# voltage_regulator.net
KiCad netlist of a schematic drawn in EasyEDA
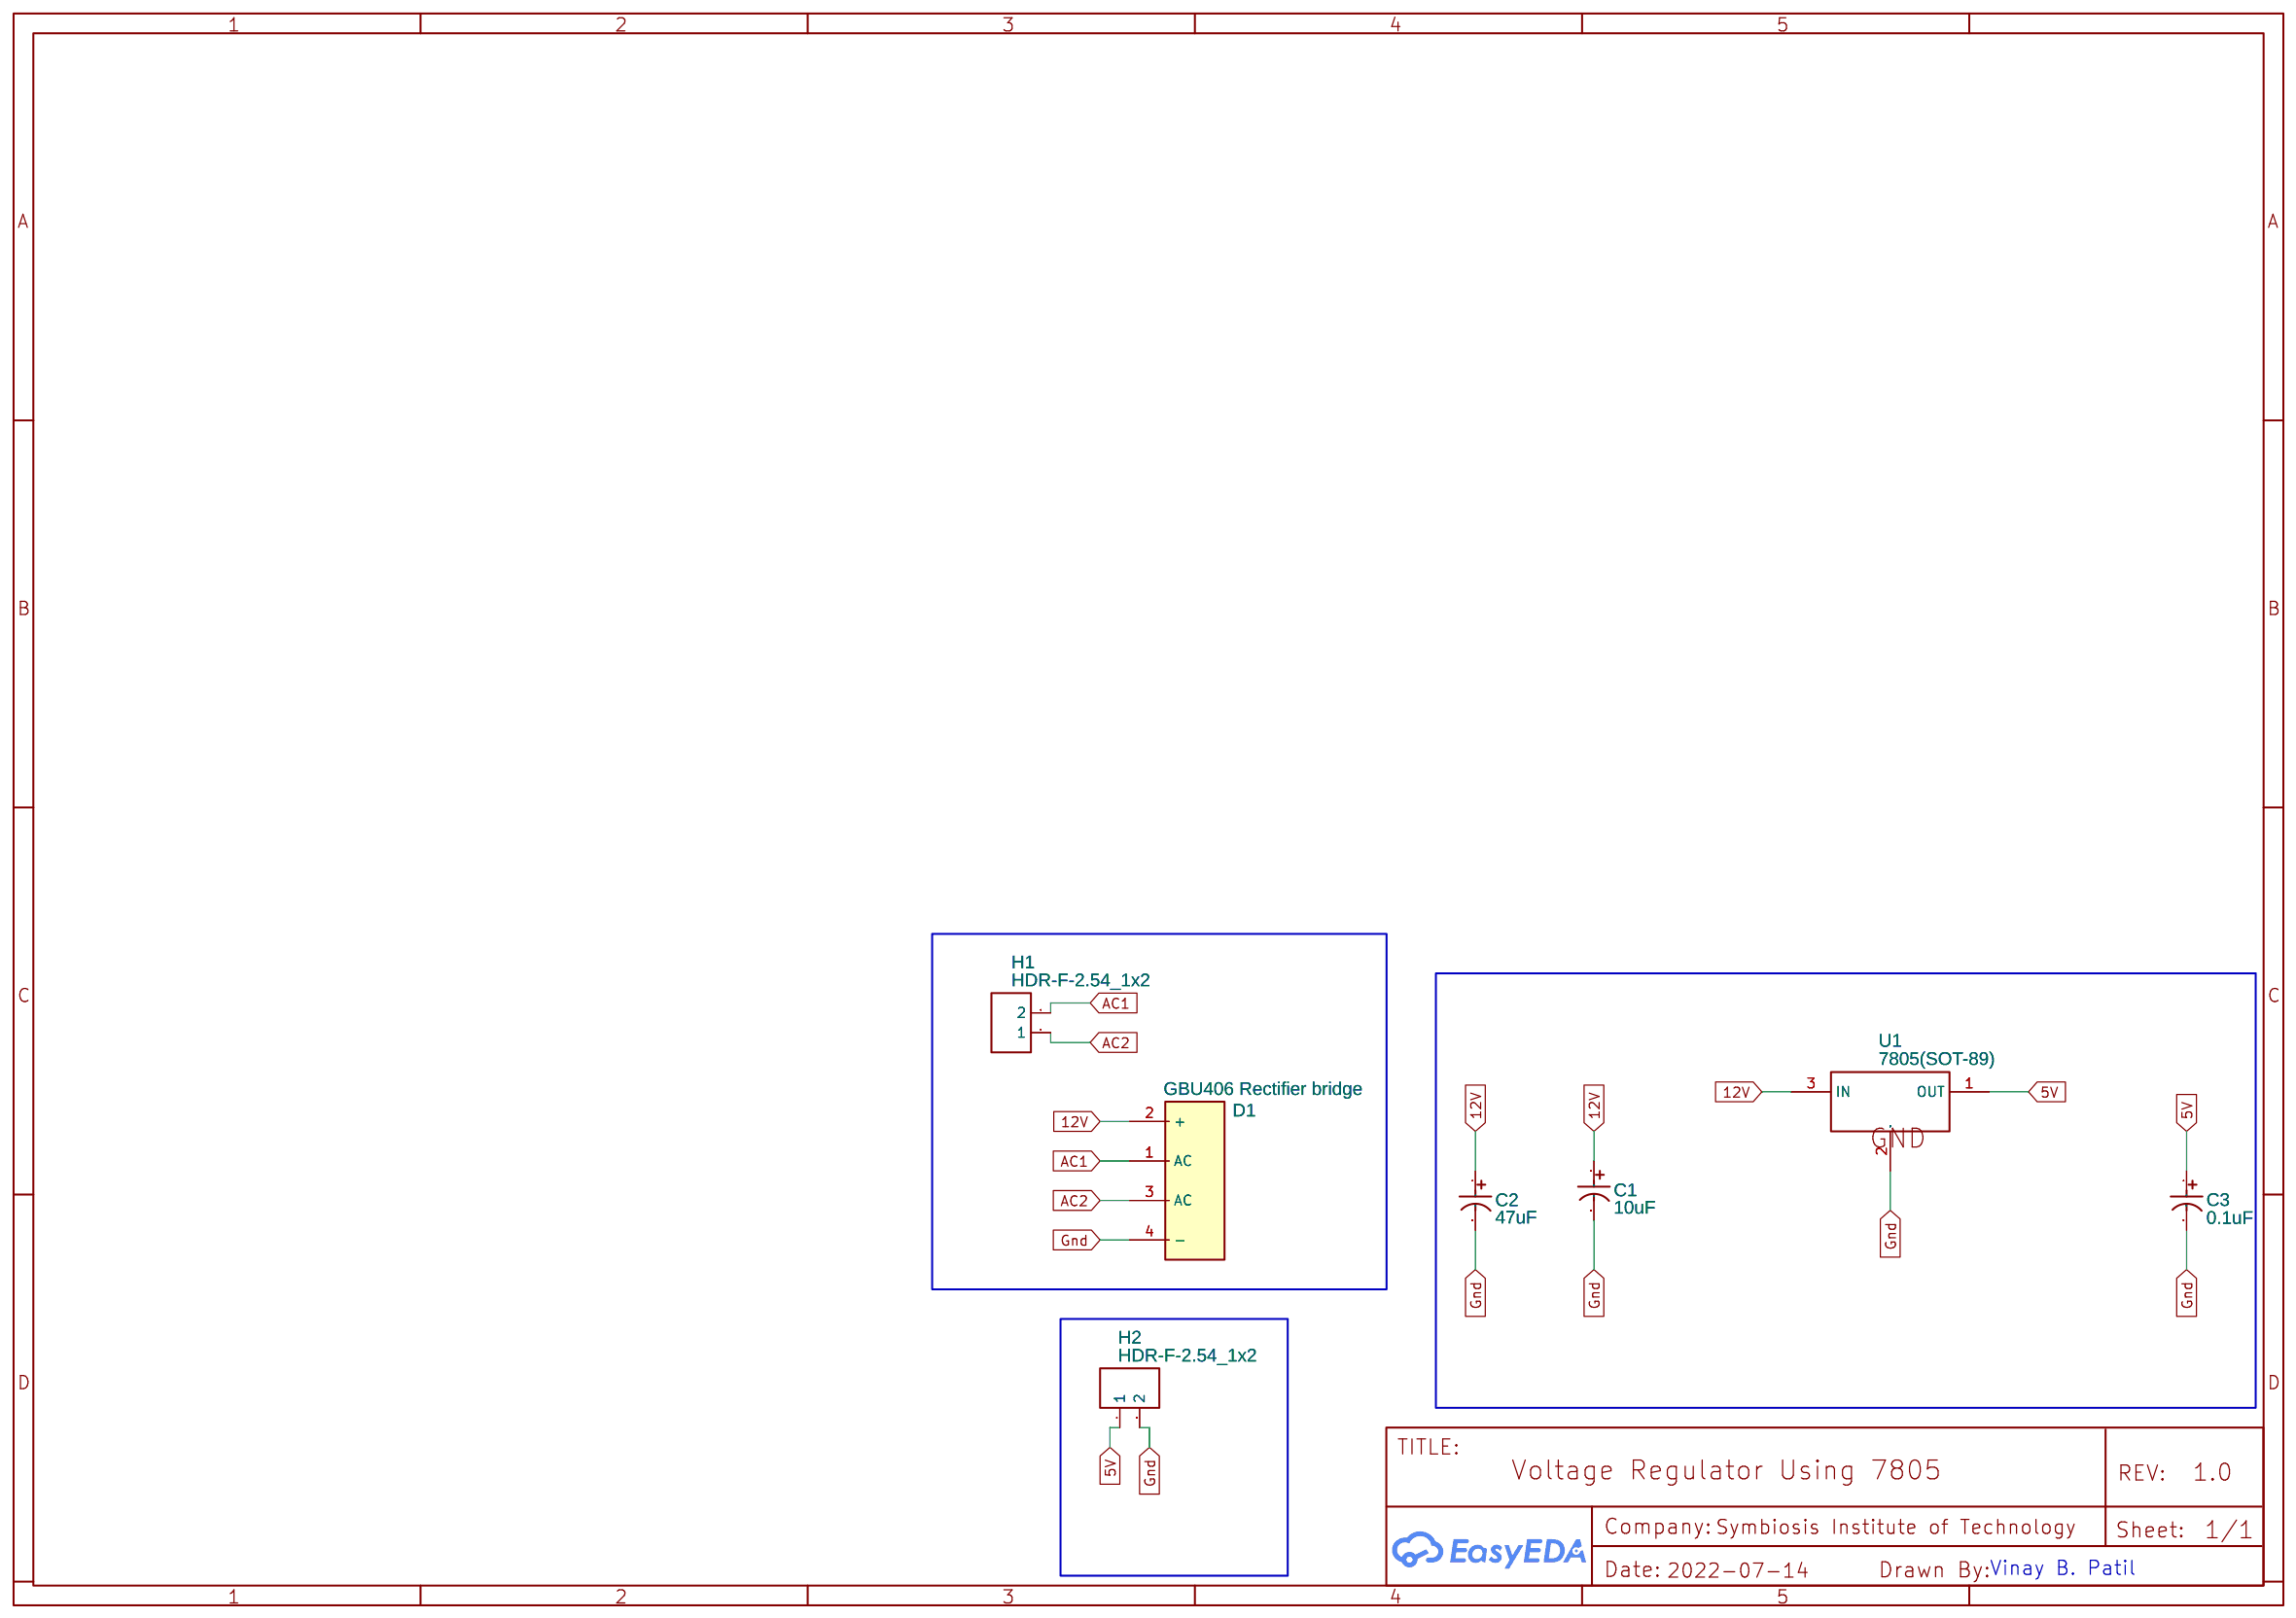
[diagram p0: schematic sheet]

(export (version "E")
  (design (tool "Eeschema 10.0.6"))
  (components
    (comp (ref "C1")
      (value "10uF")
      (fields
        (field (name "BOM_Manufacturer Part") "10uF 16V 5*11")
        (field (name "BOM_Supplier Part") "C43799")
      )
      (libsource (lib "") (part "10uF 16V 5*11"))
    )
    (comp (ref "C2")
      (value "47uF")
      (fields
        (field (name "BOM_Manufacturer Part") "47uF 16V Aluminum electrolytic capacitors")
        (field (name "BOM_Supplier Part") "C22320")
      )
      (libsource (lib "") (part "47uF 16V Aluminum electrolytic capacitors"))
    )
    (comp (ref "C3")
      (value "0.1uF")
      (fields (field (name "BOM_Manufacturer Part") "0.1UF 50V") (field (name "BOM_Supplier Part") "C28061"))
      (libsource (lib "") (part "0.1UF 50V"))
    )
    (comp (ref "D1")
      (value "GBU406 Rectifier bridge")
      (fields (field (name "BOM_Supplier Part") "C13432"))
      (libsource (lib "") (part "GBU406 Rectifier bridge"))
    )
    (comp (ref "H1")
      (value "HDR-F-2.54_1x2")
      (fields (field (name "BOM_Supplier Part") "C49661"))
      (libsource (lib "") (part "HDR-F-2.54_1x2_1"))
    )
    (comp (ref "H2")
      (value "HDR-F-2.54_1x2")
      (fields (field (name "BOM_Supplier Part") "C49661"))
      (libsource (lib "") (part "HDR-F-2.54_1x2"))
    )
    (comp (ref "U1")
      (value "7805(SOT-89)")
      (fields (field (name "BOM_Manufacturer Part") "CJ78L05") (field (name "BOM_Supplier Part") "C2079"))
      (libsource (lib "") (part "7805(SOT-89)"))
    )
  )
  (nets
    (net (code "1") (name "5V") (class "Default")
      (node (ref "C3") (pin "1") (pinfunction "1_1") (pintype "input"))
      (node (ref "H2") (pin "1") (pinfunction "1_1") (pintype "input"))
      (node (ref "U1") (pin "1") (pinfunction "OUT_1") (pintype "passive"))
    )
    (net (code "2") (name "12V") (class "Default")
      (node (ref "C1") (pin "1") (pinfunction "1_1") (pintype "input"))
      (node (ref "C2") (pin "1") (pinfunction "1_1") (pintype "input"))
      (node (ref "D1") (pin "2") (pinfunction "+_2") (pintype "input"))
      (node (ref "U1") (pin "3") (pinfunction "IN_3") (pintype "passive"))
    )
    (net (code "3") (name "AC1") (class "Default")
      (node (ref "D1") (pin "1") (pinfunction "AC_1") (pintype "input"))
      (node (ref "H1") (pin "2") (pinfunction "2_2") (pintype "input"))
    )
    (net (code "4") (name "AC2") (class "Default")
      (node (ref "D1") (pin "3") (pinfunction "AC_3") (pintype "input"))
      (node (ref "H1") (pin "1") (pinfunction "1_1") (pintype "input"))
    )
    (net (code "5") (name "Gnd") (class "Default")
      (node (ref "C1") (pin "2") (pinfunction "2_2") (pintype "input"))
      (node (ref "C2") (pin "2") (pinfunction "2_2") (pintype "input"))
      (node (ref "C3") (pin "2") (pinfunction "2_2") (pintype "input"))
      (node (ref "D1") (pin "4") (pinfunction "-_4") (pintype "input"))
      (node (ref "H2") (pin "2") (pinfunction "2_2") (pintype "input"))
      (node (ref "U1") (pin "2") (pinfunction "GND_2") (pintype "passive"))
    )
  )
)
